# 02_-ESP32.net
KiCad netlist of a schematic drawn in Altium Designer
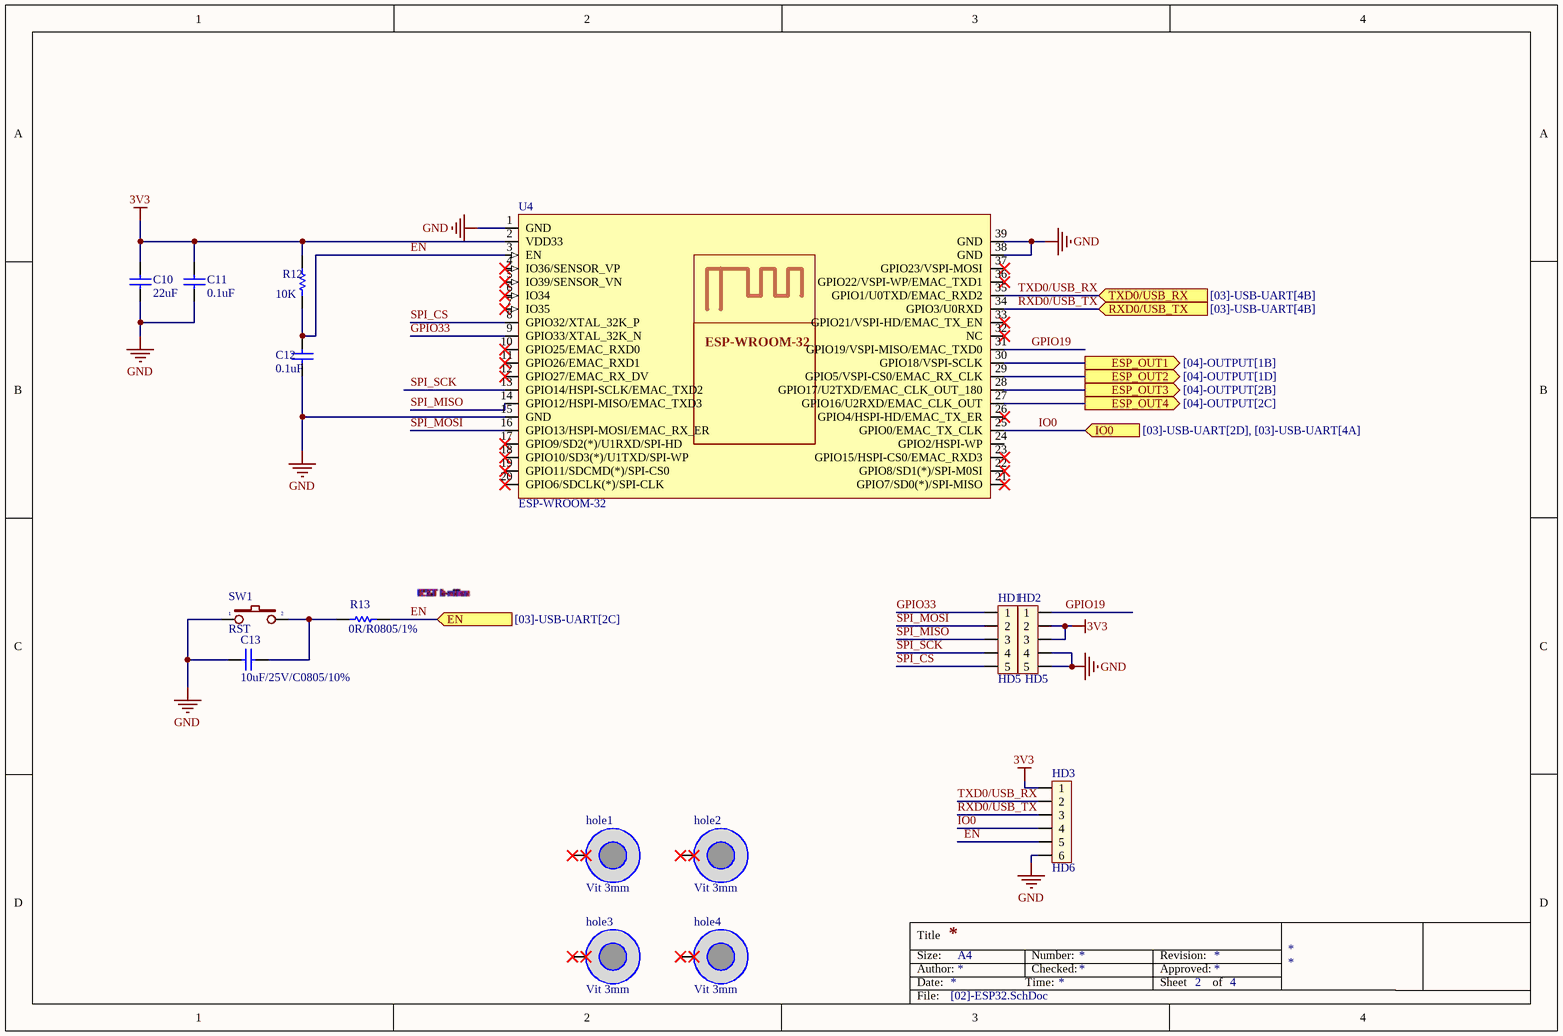
[diagram p0: [02]-ESP32.SchDoc]

(export (version "E")
  (design (tool "Eeschema 10.0.6"))
  (components
    (comp (ref "C10")
      (value "22uF")
      (footprint "CAP_CERA_C2012(CC0805INCH)")
      (description "22µF ±20% 25V Ceramic Capacitor X5R 0805 (2012 Metric)")
      (fields (field (name "MANUFACTURER") "Tariff Applied"))
      (libsource (lib "Mach o cam dien thong minh") (part "0.1uF/50V/C0603/10%_1"))
    )
    (comp (ref "C11")
      (value "0.1uF")
      (footprint "CAP_CERA_C2012(CC0805INCH)")
      (description "0.1µF ±10% 25V Ceramic Capacitor X7R 0805 (2012 Metric)")
      (libsource (lib "Mach o cam dien thong minh") (part "0.1uF/50V/C0603/10%_2"))
    )
    (comp (ref "C12")
      (value "0.1uF")
      (footprint "CAP_CERA_C2012(CC0805INCH)")
      (description "0.1µF ±10% 25V Ceramic Capacitor X7R 0805 (2012 Metric)")
      (libsource (lib "Mach o cam dien thong minh") (part "0.1uF/50V/C0603/10%_2"))
    )
    (comp (ref "C13")
      (value "10uF/25V/C0805/10%")
      (footprint "CAP_CERA_C2012(CC0805INCH)")
      (description "0.1µF ±10% 25V Ceramic Capacitor X7R 0805 (2012 Metric)")
      (libsource (lib "Mach o cam dien thong minh") (part "0.1uF/50V/C0603/10%_6"))
    )
    (comp (ref "HD1")
      (value "HD5")
      (footprint "LPSON_CON:Header_5")
      (description "Header 5")
      (fields (field (name "CREAT BY") "VanDungEvn@Gmail.com"))
      (libsource (lib "lpson") (part "Header5"))
    )
    (comp (ref "HD2")
      (value "HD5")
      (footprint "LPSON_CON:Header_5")
      (description "Header 5")
      (fields (field (name "CREAT BY") "VanDungEvn@Gmail.com"))
      (libsource (lib "") (part "Header5_1"))
    )
    (comp (ref "HD3")
      (value "HD6")
      (footprint "Header_6")
      (description "Header 6")
      (fields (field (name "CREAT BY") "VanDungEvn@Gmail.com"))
      (libsource (lib "lpson") (part "Header6"))
    )
    (comp (ref "hole1")
      (value "Vit 3mm")
      (footprint "Screw 3.0")
      (libsource (lib "Mach o cam dien thong minh") (part "Vit 3mm"))
    )
    (comp (ref "hole2")
      (value "Vit 3mm")
      (footprint "Screw 3.0")
      (libsource (lib "Mach o cam dien thong minh") (part "Vit 3mm"))
    )
    (comp (ref "hole3")
      (value "Vit 3mm")
      (footprint "Screw 3.0")
      (libsource (lib "Mach o cam dien thong minh") (part "Vit 3mm"))
    )
    (comp (ref "hole4")
      (value "Vit 3mm")
      (footprint "Screw 3.0")
      (libsource (lib "Mach o cam dien thong minh") (part "Vit 3mm"))
    )
    (comp (ref "R12")
      (value "10K")
      (footprint "Res 0805 SMD")
      (description "10 kOhms ±1% 0.125W, 1/8W Chip Resistor 0805 (2012 Metric) Thick Film")
      (libsource (lib "Mach o cam dien thong minh") (part "34.8K/R0805/1%_2"))
    )
    (comp (ref "R13")
      (value "0R/R0805/1%")
      (footprint "Res 0805 SMD")
      (description "0 Ohms Jumper 0.125W, 1/8W Chip Resistor 0805 (2012 Metric) Automotive AEC-Q200 Thick Film")
      (libsource (lib "Mach o cam dien thong minh") (part "200K/R0603/1%_1"))
    )
    (comp (ref "SW1")
      (value "RST")
      (footprint "Button 3x4mm")
      (description "SWITCH TACTILE SPST-NO 0.05A 12V")
      (libsource (lib "Mach o cam dien thong minh") (part "SW2"))
    )
    (comp (ref "U4")
      (value "ESP-WROOM-32")
      (footprint "ESP32 WROOM")
      (libsource (lib "lpson") (part "ESP-WROOM-32"))
    )
  )
  (nets
    (net (code "1") (name "/EN") (class "Default")
      (node (ref "C12") (pin "2") (pinfunction "2_2") (pintype "passive"))
      (node (ref "HD3") (pin "5") (pinfunction "5_5") (pintype "passive"))
      (node (ref "R12") (pin "1") (pinfunction "1_1") (pintype "passive"))
      (node (ref "R13") (pin "2") (pinfunction "2_2") (pintype "passive"))
      (node (ref "U4") (pin "3") (pinfunction "EN_3") (pintype "input"))
    )
    (net (code "2") (name "/ESP_OUT1") (class "Default")
      (node (ref "U4") (pin "30") (pinfunction "GPIO18/VSPI-SCLK_30") (pintype "passive"))
    )
    (net (code "3") (name "/ESP_OUT2") (class "Default")
      (node (ref "U4") (pin "29") (pinfunction "GPIO5/VSPI-CS0/EMAC_RX_CLK_29") (pintype "passive"))
    )
    (net (code "4") (name "/ESP_OUT3") (class "Default")
      (node (ref "U4") (pin "28") (pinfunction "GPIO17/U2TXD/EMAC_CLK_OUT_180_28") (pintype "passive"))
    )
    (net (code "5") (name "/ESP_OUT4") (class "Default")
      (node (ref "U4") (pin "27") (pinfunction "GPIO16/U2RXD/EMAC_CLK_OUT_27") (pintype "passive"))
    )
    (net (code "6") (name "/GPIO19") (class "Default")
      (node (ref "HD2") (pin "1") (pinfunction "1_1") (pintype "passive"))
      (node (ref "U4") (pin "31") (pinfunction "GPIO19/VSPI-MISO/EMAC_TXD0_31") (pintype "passive"))
    )
    (net (code "7") (name "/GPIO33") (class "Default")
      (node (ref "HD1") (pin "1") (pinfunction "1_1") (pintype "passive"))
      (node (ref "U4") (pin "9") (pinfunction "GPIO33/XTAL_32K_N_9") (pintype "passive"))
    )
    (net (code "8") (name "/IO0") (class "Default")
      (node (ref "HD3") (pin "4") (pinfunction "4_4") (pintype "passive"))
      (node (ref "U4") (pin "25") (pinfunction "GPIO0/EMAC_TX_CLK_25") (pintype "passive"))
    )
    (net (code "9") (name "/RXD0{slash}USB_TX") (class "Default")
      (node (ref "HD3") (pin "3") (pinfunction "3_3") (pintype "passive"))
      (node (ref "U4") (pin "34") (pinfunction "GPIO3/U0RXD_34") (pintype "passive"))
    )
    (net (code "10") (name "/SPI_CS") (class "Default")
      (node (ref "HD1") (pin "5") (pinfunction "5_5") (pintype "passive"))
      (node (ref "U4") (pin "8") (pinfunction "GPIO32/XTAL_32K_P_8") (pintype "passive"))
    )
    (net (code "11") (name "/SPI_MISO") (class "Default")
      (node (ref "HD1") (pin "3") (pinfunction "3_3") (pintype "passive"))
      (node (ref "U4") (pin "14") (pinfunction "GPIO12/HSPI-MISO/EMAC_TXD3_14") (pintype "passive"))
    )
    (net (code "12") (name "/SPI_MOSI") (class "Default")
      (node (ref "HD1") (pin "2") (pinfunction "2_2") (pintype "passive"))
      (node (ref "U4") (pin "16") (pinfunction "GPIO13/HSPI-MOSI/EMAC_RX_ER_16") (pintype "passive"))
    )
    (net (code "13") (name "/SPI_SCK") (class "Default")
      (node (ref "HD1") (pin "4") (pinfunction "4_4") (pintype "passive"))
      (node (ref "U4") (pin "13") (pinfunction "GPIO14/HSPI-SCLK/EMAC_TXD2_13") (pintype "passive"))
    )
    (net (code "14") (name "/TXD0{slash}USB_RX") (class "Default")
      (node (ref "HD3") (pin "2") (pinfunction "2_2") (pintype "passive"))
      (node (ref "U4") (pin "35") (pinfunction "GPIO1/U0TXD/EMAC_RXD2_35") (pintype "passive"))
    )
    (net (code "15") (name "3V3") (class "Default")
      (node (ref "C10") (pin "2") (pinfunction "2_2") (pintype "passive"))
      (node (ref "C11") (pin "2") (pinfunction "2_2") (pintype "passive"))
      (node (ref "HD2") (pin "2") (pinfunction "2_2") (pintype "passive"))
      (node (ref "HD2") (pin "3") (pinfunction "3_3") (pintype "passive"))
      (node (ref "HD3") (pin "1") (pinfunction "1_1") (pintype "passive"))
      (node (ref "R12") (pin "2") (pinfunction "2_2") (pintype "passive"))
      (node (ref "U4") (pin "2") (pinfunction "VDD33_2") (pintype "passive"))
    )
    (net (code "16") (name "GND") (class "Default")
      (node (ref "C10") (pin "1") (pinfunction "1_1") (pintype "passive"))
      (node (ref "C11") (pin "1") (pinfunction "1_1") (pintype "passive"))
      (node (ref "C12") (pin "1") (pinfunction "1_1") (pintype "passive"))
      (node (ref "C13") (pin "1") (pinfunction "1_1") (pintype "passive"))
      (node (ref "HD2") (pin "4") (pinfunction "4_4") (pintype "passive"))
      (node (ref "HD2") (pin "5") (pinfunction "5_5") (pintype "passive"))
      (node (ref "HD3") (pin "6") (pinfunction "6_6") (pintype "passive"))
      (node (ref "SW1") (pin "1") (pinfunction "1_1") (pintype "passive"))
      (node (ref "U4") (pin "1") (pinfunction "GND_1") (pintype "passive"))
      (node (ref "U4") (pin "15") (pinfunction "GND_15") (pintype "passive"))
      (node (ref "U4") (pin "38") (pinfunction "GND_38") (pintype "passive"))
      (node (ref "U4") (pin "39") (pinfunction "GND_39") (pintype "passive"))
    )
    (net (code "17") (name "Net-(C13-Pad2)") (class "Default")
      (node (ref "C13") (pin "2") (pinfunction "2_2") (pintype "passive"))
      (node (ref "R13") (pin "1") (pinfunction "1_1") (pintype "passive"))
      (node (ref "SW1") (pin "2") (pinfunction "2_2") (pintype "passive"))
    )
    (net (code "18") (name "unconnected-(U4-GPIO2{slash}HSPI-WP-Pad24)") (class "Default")
      (node (ref "U4") (pin "24") (pinfunction "GPIO2/HSPI-WP_24") (pintype "passive"))
    )
    (net (code "19") (name "unconnected-(U4-GPIO4{slash}HSPI-HD{slash}EMAC_TX_ER-Pad26)") (class "Default")
      (node (ref "U4") (pin "26") (pinfunction "GPIO4/HSPI-HD/EMAC_TX_ER_26") (pintype "passive+no_connect"))
    )
    (net (code "20") (name "unconnected-(U4-GPIO6{slash}SDCLK(*){slash}SPI-CLK-Pad20)") (class "Default")
      (node (ref "U4") (pin "20") (pinfunction "GPIO6/SDCLK(*)/SPI-CLK_20") (pintype "passive+no_connect"))
    )
    (net (code "21") (name "unconnected-(U4-GPIO7{slash}SD0(*){slash}SPI-MISO-Pad21)") (class "Default")
      (node (ref "U4") (pin "21") (pinfunction "GPIO7/SD0(*)/SPI-MISO_21") (pintype "passive+no_connect"))
    )
    (net (code "22") (name "unconnected-(U4-GPIO8{slash}SD1(*){slash}SPI-M0SI-Pad22)") (class "Default")
      (node (ref "U4") (pin "22") (pinfunction "GPIO8/SD1(*)/SPI-M0SI_22") (pintype "passive+no_connect"))
    )
    (net (code "23") (name "unconnected-(U4-GPIO9{slash}SD2(*){slash}U1RXD{slash}SPI-HD-Pad17)") (class "Default")
      (node (ref "U4") (pin "17") (pinfunction "GPIO9/SD2(*)/U1RXD/SPI-HD_17") (pintype "passive+no_connect"))
    )
    (net (code "24") (name "unconnected-(U4-GPIO10{slash}SD3(*){slash}U1TXD{slash}SPI-WP-Pad18)") (class "Default")
      (node (ref "U4") (pin "18") (pinfunction "GPIO10/SD3(*)/U1TXD/SPI-WP_18") (pintype "passive+no_connect"))
    )
    (net (code "25") (name "unconnected-(U4-GPIO11{slash}SDCMD(*){slash}SPI-CS0-Pad19)") (class "Default")
      (node (ref "U4") (pin "19") (pinfunction "GPIO11/SDCMD(*)/SPI-CS0_19") (pintype "passive+no_connect"))
    )
    (net (code "26") (name "unconnected-(U4-GPIO15{slash}HSPI-CS0{slash}EMAC_RXD3-Pad23)") (class "Default")
      (node (ref "U4") (pin "23") (pinfunction "GPIO15/HSPI-CS0/EMAC_RXD3_23") (pintype "passive+no_connect"))
    )
    (net (code "27") (name "unconnected-(U4-GPIO21{slash}VSPI-HD{slash}EMAC_TX_EN-Pad33)") (class "Default")
      (node (ref "U4") (pin "33") (pinfunction "GPIO21/VSPI-HD/EMAC_TX_EN_33") (pintype "passive+no_connect"))
    )
    (net (code "28") (name "unconnected-(U4-GPIO22{slash}VSPI-WP{slash}EMAC_TXD1-Pad36)") (class "Default")
      (node (ref "U4") (pin "36") (pinfunction "GPIO22/VSPI-WP/EMAC_TXD1_36") (pintype "passive+no_connect"))
    )
    (net (code "29") (name "unconnected-(U4-GPIO23{slash}VSPI-MOSI-Pad37)") (class "Default")
      (node (ref "U4") (pin "37") (pinfunction "GPIO23/VSPI-MOSI_37") (pintype "passive+no_connect"))
    )
    (net (code "30") (name "unconnected-(U4-GPIO25{slash}EMAC_RXD0-Pad10)") (class "Default")
      (node (ref "U4") (pin "10") (pinfunction "GPIO25/EMAC_RXD0_10") (pintype "passive+no_connect"))
    )
    (net (code "31") (name "unconnected-(U4-GPIO26{slash}EMAC_RXD1-Pad11)") (class "Default")
      (node (ref "U4") (pin "11") (pinfunction "GPIO26/EMAC_RXD1_11") (pintype "passive+no_connect"))
    )
    (net (code "32") (name "unconnected-(U4-GPIO27{slash}EMAC_RX_DV-Pad12)") (class "Default")
      (node (ref "U4") (pin "12") (pinfunction "GPIO27/EMAC_RX_DV_12") (pintype "passive+no_connect"))
    )
    (net (code "33") (name "unconnected-(U4-IO34-Pad6)") (class "Default")
      (node (ref "U4") (pin "6") (pinfunction "IO34_6") (pintype "input+no_connect"))
    )
    (net (code "34") (name "unconnected-(U4-IO35-Pad7)") (class "Default")
      (node (ref "U4") (pin "7") (pinfunction "IO35_7") (pintype "input+no_connect"))
    )
    (net (code "35") (name "unconnected-(U4-IO36{slash}SENSOR_VP-Pad4)") (class "Default")
      (node (ref "U4") (pin "4") (pinfunction "IO36/SENSOR_VP_4") (pintype "input+no_connect"))
    )
    (net (code "36") (name "unconnected-(U4-IO39{slash}SENSOR_VN-Pad5)") (class "Default")
      (node (ref "U4") (pin "5") (pinfunction "IO39/SENSOR_VN_5") (pintype "input+no_connect"))
    )
    (net (code "37") (name "unconnected-(U4-NC-Pad32)") (class "Default")
      (node (ref "U4") (pin "32") (pinfunction "NC_32") (pintype "passive+no_connect"))
    )
    (net (code "38") (name "unconnected-(hole1-hole-Pad1)") (class "Default")
      (node (ref "hole1") (pin "1") (pinfunction "hole_1") (pintype "passive+no_connect"))
    )
    (net (code "39") (name "unconnected-(hole2-hole-Pad1)") (class "Default")
      (node (ref "hole2") (pin "1") (pinfunction "hole_1") (pintype "passive+no_connect"))
    )
    (net (code "40") (name "unconnected-(hole3-hole-Pad1)") (class "Default")
      (node (ref "hole3") (pin "1") (pinfunction "hole_1") (pintype "passive+no_connect"))
    )
    (net (code "41") (name "unconnected-(hole4-hole-Pad1)") (class "Default")
      (node (ref "hole4") (pin "1") (pinfunction "hole_1") (pintype "passive+no_connect"))
    )
  )
)
